# BumpSensors.net
KiCad netlist of a schematic drawn in Altium Designer
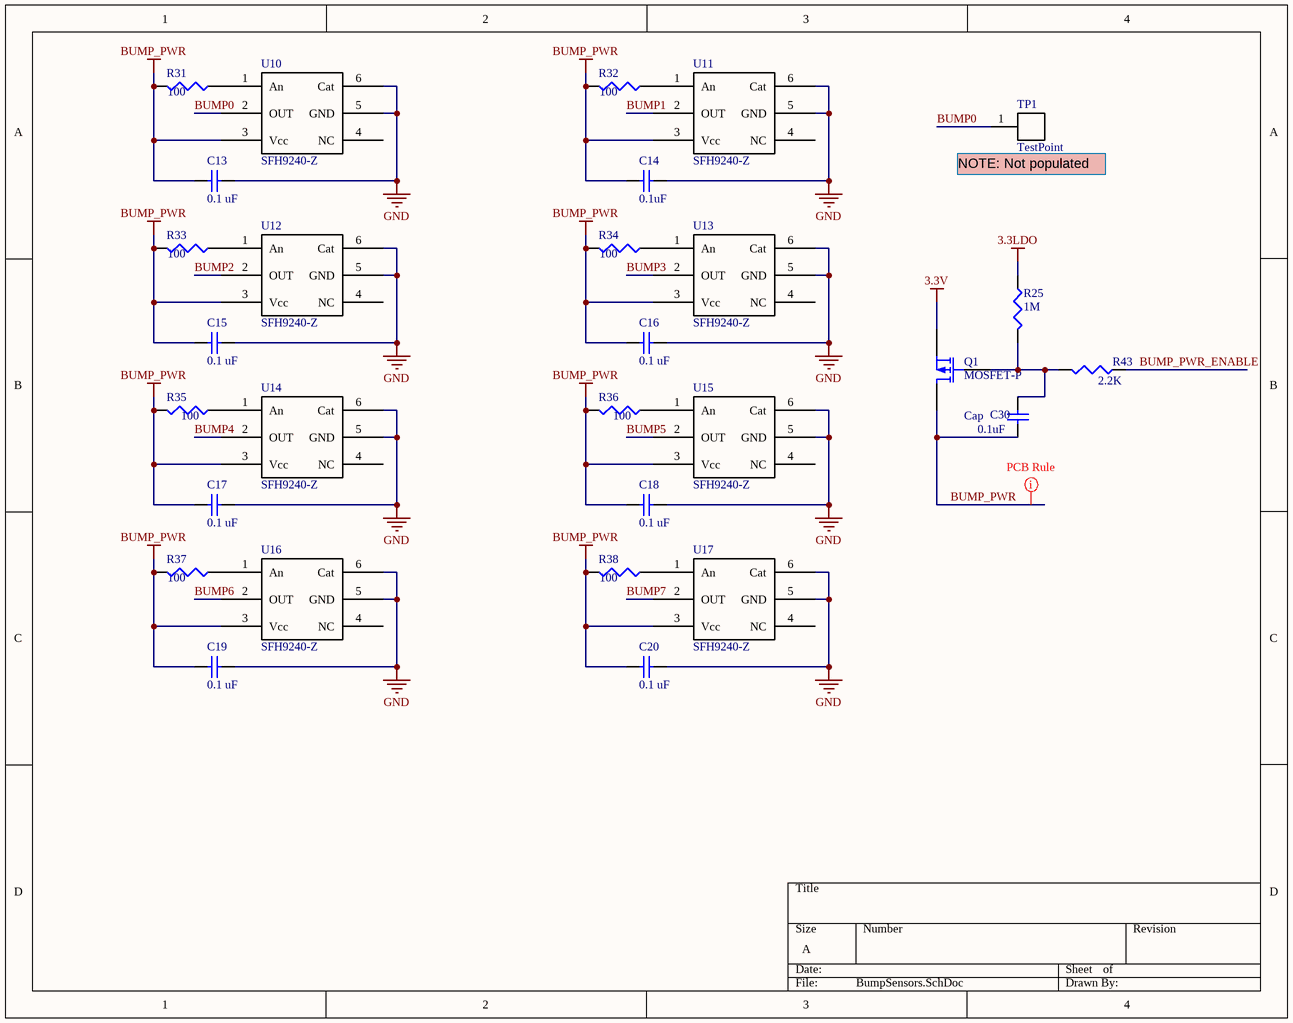
[diagram p0: BumpSensors.SchDoc]

(export (version "E")
  (design (tool "Eeschema 10.0.6"))
  (components
    (comp (ref "C13")
      (value "0.1 uF")
      (footprint "CAPC1005L")
      (description "Capacitor (Semiconductor SIM Model)")
      (fields (field (name "Comment") "Cap Semi") (field (name "PUBLISHER") "Altium Limited"))
      (libsource (lib "Miscellaneous Devices") (part "Cap Semi"))
    )
    (comp (ref "C14")
      (value "0.1uF")
      (footprint "CAPC1005L")
      (description "Capacitor (Semiconductor SIM Model)")
      (fields (field (name "Comment") "Cap Semi") (field (name "PUBLISHER") "Altium Limited"))
      (libsource (lib "Miscellaneous Devices") (part "Cap Semi"))
    )
    (comp (ref "C15")
      (value "0.1 uF")
      (footprint "CAPC1005L")
      (description "Capacitor (Semiconductor SIM Model)")
      (fields (field (name "Comment") "Cap Semi") (field (name "PUBLISHER") "Altium Limited"))
      (libsource (lib "Miscellaneous Devices") (part "Cap Semi"))
    )
    (comp (ref "C16")
      (value "0.1 uF")
      (footprint "CAPC1005L")
      (description "Capacitor (Semiconductor SIM Model)")
      (fields (field (name "Comment") "Cap Semi") (field (name "PUBLISHER") "Altium Limited"))
      (libsource (lib "Miscellaneous Devices") (part "Cap Semi"))
    )
    (comp (ref "C17")
      (value "0.1 uF")
      (footprint "CAPC1005L")
      (description "Capacitor (Semiconductor SIM Model)")
      (fields (field (name "Comment") "Cap Semi") (field (name "PUBLISHER") "Altium Limited"))
      (libsource (lib "Miscellaneous Devices") (part "Cap Semi"))
    )
    (comp (ref "C18")
      (value "0.1 uF")
      (footprint "CAPC1005L")
      (description "Capacitor (Semiconductor SIM Model)")
      (fields (field (name "Comment") "Cap Semi") (field (name "PUBLISHER") "Altium Limited"))
      (libsource (lib "Miscellaneous Devices") (part "Cap Semi"))
    )
    (comp (ref "C19")
      (value "0.1 uF")
      (footprint "CAPC1005L")
      (description "Capacitor (Semiconductor SIM Model)")
      (fields (field (name "Comment") "Cap Semi") (field (name "PUBLISHER") "Altium Limited"))
      (libsource (lib "Miscellaneous Devices") (part "Cap Semi"))
    )
    (comp (ref "C20")
      (value "0.1 uF")
      (footprint "CAPC1005L")
      (description "Capacitor (Semiconductor SIM Model)")
      (fields (field (name "Comment") "Cap Semi") (field (name "PUBLISHER") "Altium Limited"))
      (libsource (lib "Miscellaneous Devices") (part "Cap Semi"))
    )
    (comp (ref "C30")
      (value "Cap")
      (footprint "CAPC1005L")
      (description "Capacitor")
      (fields (field (name "ALTIUM_VALUE") "0.1uF") (field (name "PUBLISHER") "Altium Limited"))
      (libsource (lib "mrone") (part "Cap"))
    )
    (comp (ref "Q1")
      (value "MOSFET-P")
      (footprint "SOT-23")
      (description "P-Channel MOSFET")
      (fields (field (name "PUBLISHER") "Altium Limited"))
      (libsource (lib "mrone") (part "MOSFET-P"))
    )
    (comp (ref "R25")
      (value "1M")
      (footprint "J1-0603")
      (description "Resistor")
      (fields (field (name "Comment") "Res3") (field (name "PUBLISHER") "Altium Limited"))
      (libsource (lib "Miscellaneous Devices") (part "Res3"))
    )
    (comp (ref "R31")
      (value "100")
      (footprint "RESC1608L")
      (description "Resistor")
      (fields (field (name "Comment") "Res3") (field (name "PUBLISHER") "Altium Limited"))
      (libsource (lib "Miscellaneous Devices") (part "Res3"))
    )
    (comp (ref "R32")
      (value "100")
      (footprint "RESC1608L")
      (description "Resistor")
      (fields (field (name "Comment") "Res3") (field (name "PUBLISHER") "Altium Limited"))
      (libsource (lib "Miscellaneous Devices") (part "Res3"))
    )
    (comp (ref "R33")
      (value "100")
      (footprint "RESC1608L")
      (description "Resistor")
      (fields (field (name "Comment") "Res3") (field (name "PUBLISHER") "Altium Limited"))
      (libsource (lib "Miscellaneous Devices") (part "Res3"))
    )
    (comp (ref "R34")
      (value "100")
      (footprint "RESC1608L")
      (description "Resistor")
      (fields (field (name "Comment") "Res3") (field (name "PUBLISHER") "Altium Limited"))
      (libsource (lib "Miscellaneous Devices") (part "Res3"))
    )
    (comp (ref "R35")
      (value "100")
      (footprint "RESC1608L")
      (description "Resistor")
      (fields (field (name "Comment") "Res3") (field (name "PUBLISHER") "Altium Limited"))
      (libsource (lib "Miscellaneous Devices") (part "Res3"))
    )
    (comp (ref "R36")
      (value "100")
      (footprint "RESC1608L")
      (description "Resistor")
      (fields (field (name "Comment") "Res3") (field (name "PUBLISHER") "Altium Limited"))
      (libsource (lib "Miscellaneous Devices") (part "Res3"))
    )
    (comp (ref "R37")
      (value "100")
      (footprint "RESC1608L")
      (description "Resistor")
      (fields (field (name "Comment") "Res3") (field (name "PUBLISHER") "Altium Limited"))
      (libsource (lib "Miscellaneous Devices") (part "Res3"))
    )
    (comp (ref "R38")
      (value "100")
      (footprint "RESC1608L")
      (description "Resistor")
      (fields (field (name "Comment") "Res3") (field (name "PUBLISHER") "Altium Limited"))
      (libsource (lib "Miscellaneous Devices") (part "Res3"))
    )
    (comp (ref "R43")
      (value "2.2K")
      (footprint "J1-0603")
      (description "Resistor")
      (fields (field (name "Comment") "Res3") (field (name "PUBLISHER") "Altium Limited"))
      (libsource (lib "Miscellaneous Devices") (part "Res3"))
    )
    (comp (ref "TP1")
      (value "TestPoint")
      (footprint "TestPoint")
      (libsource (lib "mrone") (part "TestPoint"))
    )
    (comp (ref "U10")
      (value "SFH9240-Z")
      (footprint "SFH9240-Z")
      (libsource (lib "mrone") (part "SFH9240-Z"))
    )
    (comp (ref "U11")
      (value "SFH9240-Z")
      (footprint "SFH9240-Z")
      (libsource (lib "mrone") (part "SFH9240-Z"))
    )
    (comp (ref "U12")
      (value "SFH9240-Z")
      (footprint "SFH9240-Z")
      (libsource (lib "mrone") (part "SFH9240-Z"))
    )
    (comp (ref "U13")
      (value "SFH9240-Z")
      (footprint "SFH9240-Z")
      (libsource (lib "mrone") (part "SFH9240-Z"))
    )
    (comp (ref "U14")
      (value "SFH9240-Z")
      (footprint "SFH9240-Z")
      (libsource (lib "mrone") (part "SFH9240-Z"))
    )
    (comp (ref "U15")
      (value "SFH9240-Z")
      (footprint "SFH9240-Z")
      (libsource (lib "mrone") (part "SFH9240-Z"))
    )
    (comp (ref "U16")
      (value "SFH9240-Z")
      (footprint "SFH9240-Z")
      (libsource (lib "mrone") (part "SFH9240-Z"))
    )
    (comp (ref "U17")
      (value "SFH9240-Z")
      (footprint "SFH9240-Z")
      (libsource (lib "mrone") (part "SFH9240-Z"))
    )
  )
  (nets
    (net (code "1") (name "/BUMP0") (class "Default")
      (node (ref "TP1") (pin "1") (pintype "passive"))
      (node (ref "U10") (pin "2") (pinfunction "OUT_2") (pintype "passive"))
    )
    (net (code "2") (name "/BUMP1") (class "Default")
      (node (ref "U11") (pin "2") (pinfunction "OUT_2") (pintype "passive"))
    )
    (net (code "3") (name "/BUMP2") (class "Default")
      (node (ref "U12") (pin "2") (pinfunction "OUT_2") (pintype "passive"))
    )
    (net (code "4") (name "/BUMP3") (class "Default")
      (node (ref "U13") (pin "2") (pinfunction "OUT_2") (pintype "passive"))
    )
    (net (code "5") (name "/BUMP4") (class "Default")
      (node (ref "U14") (pin "2") (pinfunction "OUT_2") (pintype "passive"))
    )
    (net (code "6") (name "/BUMP5") (class "Default")
      (node (ref "U15") (pin "2") (pinfunction "OUT_2") (pintype "passive"))
    )
    (net (code "7") (name "/BUMP6") (class "Default")
      (node (ref "U16") (pin "2") (pinfunction "OUT_2") (pintype "passive"))
    )
    (net (code "8") (name "/BUMP7") (class "Default")
      (node (ref "U17") (pin "2") (pinfunction "OUT_2") (pintype "passive"))
    )
    (net (code "9") (name "/BUMP_PWR_ENABLE") (class "Default")
      (node (ref "R43") (pin "1") (pinfunction "1_1") (pintype "passive"))
    )
    (net (code "10") (name "3.3LDO") (class "Default")
      (node (ref "R25") (pin "1") (pinfunction "1_1") (pintype "passive"))
    )
    (net (code "11") (name "3.3V") (class "Default")
      (node (ref "Q1") (pin "2") (pinfunction "S_2") (pintype "passive"))
    )
    (net (code "12") (name "BUMP_PWR") (class "Default")
      (node (ref "C13") (pin "2") (pinfunction "2_2") (pintype "passive"))
      (node (ref "C14") (pin "2") (pinfunction "2_2") (pintype "passive"))
      (node (ref "C15") (pin "2") (pinfunction "2_2") (pintype "passive"))
      (node (ref "C16") (pin "2") (pinfunction "2_2") (pintype "passive"))
      (node (ref "C17") (pin "2") (pinfunction "2_2") (pintype "passive"))
      (node (ref "C18") (pin "2") (pinfunction "2_2") (pintype "passive"))
      (node (ref "C19") (pin "2") (pinfunction "2_2") (pintype "passive"))
      (node (ref "C20") (pin "2") (pinfunction "2_2") (pintype "passive"))
      (node (ref "C30") (pin "2") (pinfunction "2_2") (pintype "passive"))
      (node (ref "Q1") (pin "3") (pinfunction "D_3") (pintype "passive"))
      (node (ref "R31") (pin "2") (pinfunction "2_2") (pintype "passive"))
      (node (ref "R32") (pin "2") (pinfunction "2_2") (pintype "passive"))
      (node (ref "R33") (pin "2") (pinfunction "2_2") (pintype "passive"))
      (node (ref "R34") (pin "2") (pinfunction "2_2") (pintype "passive"))
      (node (ref "R35") (pin "2") (pinfunction "2_2") (pintype "passive"))
      (node (ref "R36") (pin "2") (pinfunction "2_2") (pintype "passive"))
      (node (ref "R37") (pin "2") (pinfunction "2_2") (pintype "passive"))
      (node (ref "R38") (pin "2") (pinfunction "2_2") (pintype "passive"))
      (node (ref "U10") (pin "3") (pinfunction "Vcc_3") (pintype "passive"))
      (node (ref "U11") (pin "3") (pinfunction "Vcc_3") (pintype "passive"))
      (node (ref "U12") (pin "3") (pinfunction "Vcc_3") (pintype "passive"))
      (node (ref "U13") (pin "3") (pinfunction "Vcc_3") (pintype "passive"))
      (node (ref "U14") (pin "3") (pinfunction "Vcc_3") (pintype "passive"))
      (node (ref "U15") (pin "3") (pinfunction "Vcc_3") (pintype "passive"))
      (node (ref "U16") (pin "3") (pinfunction "Vcc_3") (pintype "passive"))
      (node (ref "U17") (pin "3") (pinfunction "Vcc_3") (pintype "passive"))
    )
    (net (code "13") (name "GND") (class "Default")
      (node (ref "C13") (pin "1") (pinfunction "1_1") (pintype "passive"))
      (node (ref "C14") (pin "1") (pinfunction "1_1") (pintype "passive"))
      (node (ref "C15") (pin "1") (pinfunction "1_1") (pintype "passive"))
      (node (ref "C16") (pin "1") (pinfunction "1_1") (pintype "passive"))
      (node (ref "C17") (pin "1") (pinfunction "1_1") (pintype "passive"))
      (node (ref "C18") (pin "1") (pinfunction "1_1") (pintype "passive"))
      (node (ref "C19") (pin "1") (pinfunction "1_1") (pintype "passive"))
      (node (ref "C20") (pin "1") (pinfunction "1_1") (pintype "passive"))
      (node (ref "U10") (pin "5") (pinfunction "GND_5") (pintype "passive"))
      (node (ref "U10") (pin "6") (pinfunction "Cat_6") (pintype "passive"))
      (node (ref "U11") (pin "5") (pinfunction "GND_5") (pintype "passive"))
      (node (ref "U11") (pin "6") (pinfunction "Cat_6") (pintype "passive"))
      (node (ref "U12") (pin "5") (pinfunction "GND_5") (pintype "passive"))
      (node (ref "U12") (pin "6") (pinfunction "Cat_6") (pintype "passive"))
      (node (ref "U13") (pin "5") (pinfunction "GND_5") (pintype "passive"))
      (node (ref "U13") (pin "6") (pinfunction "Cat_6") (pintype "passive"))
      (node (ref "U14") (pin "5") (pinfunction "GND_5") (pintype "passive"))
      (node (ref "U14") (pin "6") (pinfunction "Cat_6") (pintype "passive"))
      (node (ref "U15") (pin "5") (pinfunction "GND_5") (pintype "passive"))
      (node (ref "U15") (pin "6") (pinfunction "Cat_6") (pintype "passive"))
      (node (ref "U16") (pin "5") (pinfunction "GND_5") (pintype "passive"))
      (node (ref "U16") (pin "6") (pinfunction "Cat_6") (pintype "passive"))
      (node (ref "U17") (pin "5") (pinfunction "GND_5") (pintype "passive"))
      (node (ref "U17") (pin "6") (pinfunction "Cat_6") (pintype "passive"))
    )
    (net (code "14") (name "Net-(Q1-G)") (class "Default")
      (node (ref "C30") (pin "1") (pinfunction "1_1") (pintype "passive"))
      (node (ref "Q1") (pin "1") (pinfunction "G_1") (pintype "passive"))
      (node (ref "R25") (pin "2") (pinfunction "2_2") (pintype "passive"))
      (node (ref "R43") (pin "2") (pinfunction "2_2") (pintype "passive"))
    )
    (net (code "15") (name "Net-(U10-An)") (class "Default")
      (node (ref "R31") (pin "1") (pinfunction "1_1") (pintype "passive"))
      (node (ref "U10") (pin "1") (pinfunction "An_1") (pintype "passive"))
    )
    (net (code "16") (name "Net-(U11-An)") (class "Default")
      (node (ref "R32") (pin "1") (pinfunction "1_1") (pintype "passive"))
      (node (ref "U11") (pin "1") (pinfunction "An_1") (pintype "passive"))
    )
    (net (code "17") (name "Net-(U12-An)") (class "Default")
      (node (ref "R33") (pin "1") (pinfunction "1_1") (pintype "passive"))
      (node (ref "U12") (pin "1") (pinfunction "An_1") (pintype "passive"))
    )
    (net (code "18") (name "Net-(U13-An)") (class "Default")
      (node (ref "R34") (pin "1") (pinfunction "1_1") (pintype "passive"))
      (node (ref "U13") (pin "1") (pinfunction "An_1") (pintype "passive"))
    )
    (net (code "19") (name "Net-(U14-An)") (class "Default")
      (node (ref "R35") (pin "1") (pinfunction "1_1") (pintype "passive"))
      (node (ref "U14") (pin "1") (pinfunction "An_1") (pintype "passive"))
    )
    (net (code "20") (name "Net-(U15-An)") (class "Default")
      (node (ref "R36") (pin "1") (pinfunction "1_1") (pintype "passive"))
      (node (ref "U15") (pin "1") (pinfunction "An_1") (pintype "passive"))
    )
    (net (code "21") (name "Net-(U16-An)") (class "Default")
      (node (ref "R37") (pin "1") (pinfunction "1_1") (pintype "passive"))
      (node (ref "U16") (pin "1") (pinfunction "An_1") (pintype "passive"))
    )
    (net (code "22") (name "Net-(U17-An)") (class "Default")
      (node (ref "R38") (pin "1") (pinfunction "1_1") (pintype "passive"))
      (node (ref "U17") (pin "1") (pinfunction "An_1") (pintype "passive"))
    )
    (net (code "23") (name "unconnected-(U10-NC-Pad4)") (class "Default")
      (node (ref "U10") (pin "4") (pinfunction "NC_4") (pintype "passive"))
    )
    (net (code "24") (name "unconnected-(U11-NC-Pad4)") (class "Default")
      (node (ref "U11") (pin "4") (pinfunction "NC_4") (pintype "passive"))
    )
    (net (code "25") (name "unconnected-(U12-NC-Pad4)") (class "Default")
      (node (ref "U12") (pin "4") (pinfunction "NC_4") (pintype "passive"))
    )
    (net (code "26") (name "unconnected-(U13-NC-Pad4)") (class "Default")
      (node (ref "U13") (pin "4") (pinfunction "NC_4") (pintype "passive"))
    )
    (net (code "27") (name "unconnected-(U14-NC-Pad4)") (class "Default")
      (node (ref "U14") (pin "4") (pinfunction "NC_4") (pintype "passive"))
    )
    (net (code "28") (name "unconnected-(U15-NC-Pad4)") (class "Default")
      (node (ref "U15") (pin "4") (pinfunction "NC_4") (pintype "passive"))
    )
    (net (code "29") (name "unconnected-(U16-NC-Pad4)") (class "Default")
      (node (ref "U16") (pin "4") (pinfunction "NC_4") (pintype "passive"))
    )
    (net (code "30") (name "unconnected-(U17-NC-Pad4)") (class "Default")
      (node (ref "U17") (pin "4") (pinfunction "NC_4") (pintype "passive"))
    )
  )
)
